# XmegaA4U_v2_1.net
KiCad netlist of a schematic drawn in EAGLE
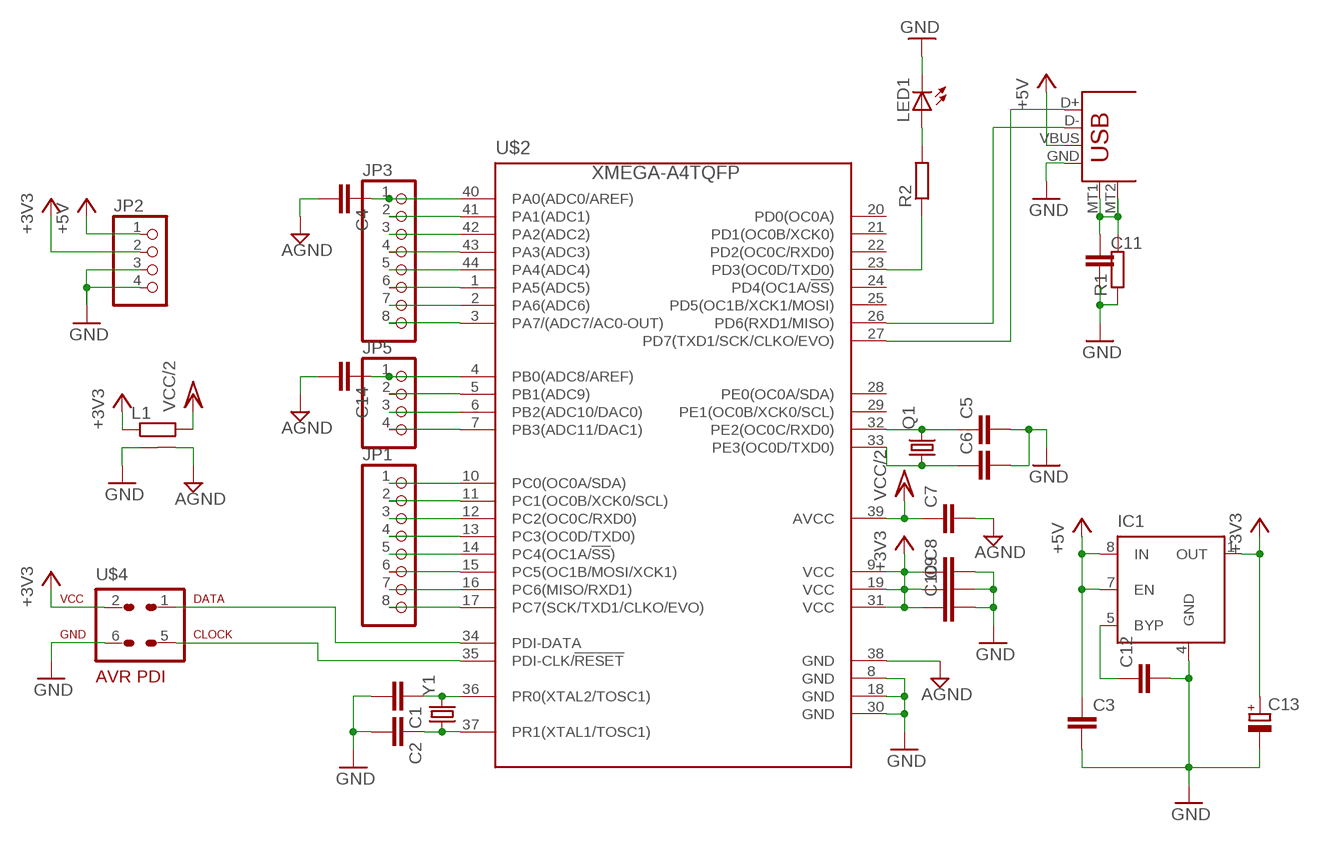
[diagram p0: schematic, sheet 1]

(export (version "E")
  (design (tool "Eeschema 10.0.6"))
  (components
    (comp (ref "C1")
      (value "C-EUC0603")
      (footprint "eagle-import:C0603")
      (libsource (lib "eagle-import") (part "C-EUC0603"))
    )
    (comp (ref "C2")
      (value "C-EUC0603")
      (footprint "eagle-import:C0603")
      (libsource (lib "eagle-import") (part "C-EUC0603"))
    )
    (comp (ref "C3")
      (value "C-EUC0805")
      (footprint "eagle-import:C0805")
      (libsource (lib "eagle-import") (part "C-EUC0805"))
    )
    (comp (ref "C4")
      (value "C-EUC0402")
      (footprint "eagle-import:C0402")
      (libsource (lib "eagle-import") (part "C-EUC0402"))
    )
    (comp (ref "C5")
      (value "C-EUC0402")
      (footprint "eagle-import:C0402")
      (libsource (lib "eagle-import") (part "C-EUC0402"))
    )
    (comp (ref "C6")
      (value "C-EUC0402")
      (footprint "eagle-import:C0402")
      (libsource (lib "eagle-import") (part "C-EUC0402"))
    )
    (comp (ref "C7")
      (value "C-EUC0603")
      (footprint "eagle-import:C0603")
      (libsource (lib "eagle-import") (part "C-EUC0603"))
    )
    (comp (ref "C8")
      (value "C-EUC0603")
      (footprint "eagle-import:C0603")
      (libsource (lib "eagle-import") (part "C-EUC0603"))
    )
    (comp (ref "C9")
      (value "C-EUC0603")
      (footprint "eagle-import:C0603")
      (libsource (lib "eagle-import") (part "C-EUC0603"))
    )
    (comp (ref "C10")
      (value "C-EUC0603")
      (footprint "eagle-import:C0603")
      (libsource (lib "eagle-import") (part "C-EUC0603"))
    )
    (comp (ref "C11")
      (value "C-EUC0603")
      (footprint "eagle-import:C0603")
      (libsource (lib "eagle-import") (part "C-EUC0603"))
    )
    (comp (ref "C12")
      (value "C-EUC0603")
      (footprint "eagle-import:C0603")
      (libsource (lib "eagle-import") (part "C-EUC0603"))
    )
    (comp (ref "C13")
      (value "CPOL-EUSMCA")
      (footprint "eagle-import:SMC_A")
      (libsource (lib "eagle-import") (part "CPOL-EUSMCA"))
    )
    (comp (ref "C14")
      (value "C-EUC0402")
      (footprint "eagle-import:C0402")
      (libsource (lib "eagle-import") (part "C-EUC0402"))
    )
    (comp (ref "IC1")
      (value "TC1269")
      (footprint "eagle-import:MSOP08")
      (libsource (lib "eagle-import") (part "TC1269"))
    )
    (comp (ref "JP1")
      (value "PINHD_FIXEDPAD_ROUND-1X8")
      (footprint "eagle-import:1X08_ROUND")
      (libsource (lib "eagle-import") (part "PINHD_FIXEDPAD_ROUND-1X8"))
    )
    (comp (ref "JP2")
      (value "PINHD_FIXEDPAD_ROUND-1X4")
      (footprint "eagle-import:1X04_ROUND")
      (libsource (lib "eagle-import") (part "PINHD_FIXEDPAD_ROUND-1X4"))
    )
    (comp (ref "JP3")
      (value "PINHD_FIXEDPAD_ROUND-1X8")
      (footprint "eagle-import:1X08_ROUND")
      (libsource (lib "eagle-import") (part "PINHD_FIXEDPAD_ROUND-1X8"))
    )
    (comp (ref "JP5")
      (value "PINHD_FIXEDPAD_ROUND-1X4")
      (footprint "eagle-import:1X04_ROUND")
      (libsource (lib "eagle-import") (part "PINHD_FIXEDPAD_ROUND-1X4"))
    )
    (comp (ref "L1")
      (value "R-EU_R0603")
      (footprint "eagle-import:R0603")
      (libsource (lib "eagle-import") (part "R-EU_R0603"))
    )
    (comp (ref "LED1")
      (value "LEDCHIP-LED0603")
      (footprint "eagle-import:CHIP-LED0603")
      (libsource (lib "eagle-import") (part "LEDCHIP-LED0603"))
    )
    (comp (ref "Q1")
      (value "CRYSTALTC26V_1.00")
      (footprint "eagle-import:TC26V_1.00")
      (libsource (lib "eagle-import") (part "CRYSTALTC26V_1.00"))
    )
    (comp (ref "R1")
      (value "R-EU_R0603")
      (footprint "eagle-import:R0603")
      (libsource (lib "eagle-import") (part "R-EU_R0603"))
    )
    (comp (ref "R2")
      (value "R-EU_R0603")
      (footprint "eagle-import:R0603")
      (libsource (lib "eagle-import") (part "R-EU_R0603"))
    )
    (comp (ref "U$1")
      (value "LINE1.27X0.254MM")
      (footprint "eagle-import:LINE-1.27X0.254MM")
      (libsource (lib "eagle-import") (part "LINE1.27X0.254MM"))
    )
    (comp (ref "U$2")
      (value "XMEGA-A4TQFP")
      (footprint "eagle-import:TQFP44")
      (libsource (lib "eagle-import") (part "XMEGA-A4TQFP"))
    )
    (comp (ref "U$4")
      (value "AVR-PDIFIXED")
      (footprint "eagle-import:2X03_FIXED")
      (libsource (lib "eagle-import") (part "AVR-PDIFIXED"))
    )
    (comp (ref "U$5")
      (value "USB+SHIELDMICRO")
      (footprint "eagle-import:USB-MICROB")
      (libsource (lib "eagle-import") (part "USB+SHIELDMICRO"))
    )
    (comp (ref "Y1")
      (value "CRYSTAL5X3")
      (footprint "eagle-import:CRYSTAL-SMD-5X3")
      (libsource (lib "eagle-import") (part "CRYSTAL5X3"))
    )
  )
  (nets
    (net (code "1") (name "+3V3") (class "Default")
      (node (ref "C10") (pin "1") (pinfunction "1_1") (pintype "passive"))
      (node (ref "C13") (pin "+") (pinfunction "+_+") (pintype "passive"))
      (node (ref "C8") (pin "1") (pinfunction "1_1") (pintype "passive"))
      (node (ref "C9") (pin "1") (pinfunction "1_1") (pintype "passive"))
      (node (ref "IC1") (pin "1") (pinfunction "OUT_1") (pintype "output"))
      (node (ref "JP2") (pin "2") (pinfunction "2_2") (pintype "passive"))
      (node (ref "L1") (pin "1") (pinfunction "1_1") (pintype "passive"))
      (node (ref "U$2") (pin "19") (pinfunction "VCC_19") (pintype "power_in"))
      (node (ref "U$2") (pin "31") (pinfunction "VCC_31") (pintype "power_in"))
      (node (ref "U$2") (pin "9") (pinfunction "VCC_9") (pintype "power_in"))
      (node (ref "U$4") (pin "2") (pinfunction "2_VCC_2") (pintype "passive"))
    )
    (net (code "2") (name "+5V") (class "Default")
      (node (ref "C3") (pin "1") (pinfunction "1_1") (pintype "passive"))
      (node (ref "IC1") (pin "7") (pinfunction "EN_7") (pintype "input"))
      (node (ref "IC1") (pin "8") (pinfunction "IN_8") (pintype "input"))
      (node (ref "JP2") (pin "1") (pinfunction "1_1") (pintype "passive"))
      (node (ref "U$5") (pin "VBUS") (pinfunction "VBUS_VBUS") (pintype "bidirectional"))
    )
    (net (code "3") (name "AGND") (class "Default")
      (node (ref "C14") (pin "2") (pinfunction "2_2") (pintype "passive"))
      (node (ref "C4") (pin "2") (pinfunction "2_2") (pintype "passive"))
      (node (ref "C7") (pin "2") (pinfunction "2_2") (pintype "passive"))
      (node (ref "U$1") (pin "P$2") (pinfunction "P$2_P$2") (pintype "bidirectional"))
      (node (ref "U$2") (pin "38") (pinfunction "GND_38") (pintype "power_in"))
    )
    (net (code "4") (name "GND") (class "Default")
      (node (ref "C1") (pin "2") (pinfunction "2_2") (pintype "passive"))
      (node (ref "C10") (pin "2") (pinfunction "2_2") (pintype "passive"))
      (node (ref "C11") (pin "2") (pinfunction "2_2") (pintype "passive"))
      (node (ref "C12") (pin "2") (pinfunction "2_2") (pintype "passive"))
      (node (ref "C13") (pin "-") (pinfunction "-_-") (pintype "passive"))
      (node (ref "C2") (pin "2") (pinfunction "2_2") (pintype "passive"))
      (node (ref "C3") (pin "2") (pinfunction "2_2") (pintype "passive"))
      (node (ref "C5") (pin "2") (pinfunction "2_2") (pintype "passive"))
      (node (ref "C6") (pin "2") (pinfunction "2_2") (pintype "passive"))
      (node (ref "C8") (pin "2") (pinfunction "2_2") (pintype "passive"))
      (node (ref "C9") (pin "2") (pinfunction "2_2") (pintype "passive"))
      (node (ref "IC1") (pin "4") (pinfunction "GND_4") (pintype "power_in"))
      (node (ref "JP2") (pin "3") (pinfunction "3_3") (pintype "passive"))
      (node (ref "JP2") (pin "4") (pinfunction "4_4") (pintype "passive"))
      (node (ref "LED1") (pin "C") (pinfunction "C_C") (pintype "passive"))
      (node (ref "R1") (pin "1") (pinfunction "1_1") (pintype "passive"))
      (node (ref "U$1") (pin "P$1") (pinfunction "P$1_P$1") (pintype "bidirectional"))
      (node (ref "U$2") (pin "18") (pinfunction "GND_18") (pintype "power_in"))
      (node (ref "U$2") (pin "30") (pinfunction "GND_30") (pintype "power_in"))
      (node (ref "U$2") (pin "8") (pinfunction "GND_8") (pintype "power_in"))
      (node (ref "U$4") (pin "6") (pinfunction "6_GND_6") (pintype "passive"))
      (node (ref "U$5") (pin "GND") (pinfunction "GND_GND") (pintype "bidirectional"))
    )
    (net (code "5") (name "Net-(IC1-BYP)") (class "Default")
      (node (ref "C12") (pin "1") (pinfunction "1_1") (pintype "passive"))
      (node (ref "IC1") (pin "5") (pinfunction "BYP_5") (pintype "passive"))
    )
    (net (code "6") (name "Net-(LED1-PadA)") (class "Default")
      (node (ref "LED1") (pin "A") (pinfunction "A_A") (pintype "passive"))
      (node (ref "R2") (pin "2") (pinfunction "2_2") (pintype "passive"))
    )
    (net (code "7") (name "Net-(U$2-PA0(ADC0{slash}AREF))") (class "Default")
      (node (ref "C4") (pin "1") (pinfunction "1_1") (pintype "passive"))
      (node (ref "JP3") (pin "1") (pinfunction "1_1") (pintype "passive"))
      (node (ref "U$2") (pin "40") (pinfunction "PA0(ADC0/AREF)_40") (pintype "bidirectional"))
    )
    (net (code "8") (name "Net-(U$2-PA1(ADC1))") (class "Default")
      (node (ref "JP3") (pin "2") (pinfunction "2_2") (pintype "passive"))
      (node (ref "U$2") (pin "41") (pinfunction "PA1(ADC1)_41") (pintype "bidirectional"))
    )
    (net (code "9") (name "Net-(U$2-PA2(ADC2))") (class "Default")
      (node (ref "JP3") (pin "3") (pinfunction "3_3") (pintype "passive"))
      (node (ref "U$2") (pin "42") (pinfunction "PA2(ADC2)_42") (pintype "bidirectional"))
    )
    (net (code "10") (name "Net-(U$2-PA3(ADC3))") (class "Default")
      (node (ref "JP3") (pin "4") (pinfunction "4_4") (pintype "passive"))
      (node (ref "U$2") (pin "43") (pinfunction "PA3(ADC3)_43") (pintype "bidirectional"))
    )
    (net (code "11") (name "Net-(U$2-PA4(ADC4))") (class "Default")
      (node (ref "JP3") (pin "5") (pinfunction "5_5") (pintype "passive"))
      (node (ref "U$2") (pin "44") (pinfunction "PA4(ADC4)_44") (pintype "bidirectional"))
    )
    (net (code "12") (name "Net-(U$2-PA5(ADC5))") (class "Default")
      (node (ref "JP3") (pin "6") (pinfunction "6_6") (pintype "passive"))
      (node (ref "U$2") (pin "1") (pinfunction "PA5(ADC5)_1") (pintype "bidirectional"))
    )
    (net (code "13") (name "Net-(U$2-PA6(ADC6))") (class "Default")
      (node (ref "JP3") (pin "7") (pinfunction "7_7") (pintype "passive"))
      (node (ref "U$2") (pin "2") (pinfunction "PA6(ADC6)_2") (pintype "bidirectional"))
    )
    (net (code "14") (name "Net-(U$2-PA7{slash}(ADC7{slash}AC0-OUT))") (class "Default")
      (node (ref "JP3") (pin "8") (pinfunction "8_8") (pintype "passive"))
      (node (ref "U$2") (pin "3") (pinfunction "PA7/(ADC7/AC0-OUT)_3") (pintype "bidirectional"))
    )
    (net (code "15") (name "Net-(U$2-PB0(ADC8{slash}AREF))") (class "Default")
      (node (ref "C14") (pin "1") (pinfunction "1_1") (pintype "passive"))
      (node (ref "JP5") (pin "1") (pinfunction "1_1") (pintype "passive"))
      (node (ref "U$2") (pin "4") (pinfunction "PB0(ADC8/AREF)_4") (pintype "bidirectional"))
    )
    (net (code "16") (name "Net-(U$2-PB1(ADC9))") (class "Default")
      (node (ref "JP5") (pin "2") (pinfunction "2_2") (pintype "passive"))
      (node (ref "U$2") (pin "5") (pinfunction "PB1(ADC9)_5") (pintype "bidirectional"))
    )
    (net (code "17") (name "Net-(U$2-PB2(ADC10{slash}DAC0))") (class "Default")
      (node (ref "JP5") (pin "3") (pinfunction "3_3") (pintype "passive"))
      (node (ref "U$2") (pin "6") (pinfunction "PB2(ADC10/DAC0)_6") (pintype "bidirectional"))
    )
    (net (code "18") (name "Net-(U$2-PB3(ADC11{slash}DAC1))") (class "Default")
      (node (ref "JP5") (pin "4") (pinfunction "4_4") (pintype "passive"))
      (node (ref "U$2") (pin "7") (pinfunction "PB3(ADC11/DAC1)_7") (pintype "bidirectional"))
    )
    (net (code "19") (name "Net-(U$2-PC0(OC0A{slash}SDA))") (class "Default")
      (node (ref "JP1") (pin "1") (pinfunction "1_1") (pintype "passive"))
      (node (ref "U$2") (pin "10") (pinfunction "PC0(OC0A/SDA)_10") (pintype "bidirectional"))
    )
    (net (code "20") (name "Net-(U$2-PC1(OC0B{slash}XCK0{slash}SCL))") (class "Default")
      (node (ref "JP1") (pin "2") (pinfunction "2_2") (pintype "passive"))
      (node (ref "U$2") (pin "11") (pinfunction "PC1(OC0B/XCK0/SCL)_11") (pintype "bidirectional"))
    )
    (net (code "21") (name "Net-(U$2-PC2(OC0C{slash}RXD0))") (class "Default")
      (node (ref "JP1") (pin "3") (pinfunction "3_3") (pintype "passive"))
      (node (ref "U$2") (pin "12") (pinfunction "PC2(OC0C/RXD0)_12") (pintype "bidirectional"))
    )
    (net (code "22") (name "Net-(U$2-PC3(OC0D{slash}TXD0))") (class "Default")
      (node (ref "JP1") (pin "4") (pinfunction "4_4") (pintype "passive"))
      (node (ref "U$2") (pin "13") (pinfunction "PC3(OC0D/TXD0)_13") (pintype "bidirectional"))
    )
    (net (code "23") (name "Net-(U$2-PC4(OC1A{slash}~{SS}))") (class "Default")
      (node (ref "JP1") (pin "5") (pinfunction "5_5") (pintype "passive"))
      (node (ref "U$2") (pin "14") (pinfunction "PC4(OC1A/~{SS})_14") (pintype "bidirectional"))
    )
    (net (code "24") (name "Net-(U$2-PC5(OC1B{slash}MOSI{slash}XCK1))") (class "Default")
      (node (ref "JP1") (pin "6") (pinfunction "6_6") (pintype "passive"))
      (node (ref "U$2") (pin "15") (pinfunction "PC5(OC1B/MOSI/XCK1)_15") (pintype "bidirectional"))
    )
    (net (code "25") (name "Net-(U$2-PC6(MISO{slash}RXD1))") (class "Default")
      (node (ref "JP1") (pin "7") (pinfunction "7_7") (pintype "passive"))
      (node (ref "U$2") (pin "16") (pinfunction "PC6(MISO/RXD1)_16") (pintype "bidirectional"))
    )
    (net (code "26") (name "Net-(U$2-PC7(SCK{slash}TXD1{slash}CLKO{slash}EVO))") (class "Default")
      (node (ref "JP1") (pin "8") (pinfunction "8_8") (pintype "passive"))
      (node (ref "U$2") (pin "17") (pinfunction "PC7(SCK/TXD1/CLKO/EVO)_17") (pintype "bidirectional"))
    )
    (net (code "27") (name "Net-(U$2-PD3(OC0D{slash}TXD0))") (class "Default")
      (node (ref "R2") (pin "1") (pinfunction "1_1") (pintype "passive"))
      (node (ref "U$2") (pin "23") (pinfunction "PD3(OC0D/TXD0)_23") (pintype "bidirectional"))
    )
    (net (code "28") (name "Net-(U$2-PD6(RXD1{slash}MISO))") (class "Default")
      (node (ref "U$2") (pin "26") (pinfunction "PD6(RXD1/MISO)_26") (pintype "bidirectional"))
      (node (ref "U$5") (pin "D-") (pinfunction "D-_D-") (pintype "bidirectional"))
    )
    (net (code "29") (name "Net-(U$2-PD7(TXD1{slash}SCK{slash}CLKO{slash}EVO))") (class "Default")
      (node (ref "U$2") (pin "27") (pinfunction "PD7(TXD1/SCK/CLKO/EVO)_27") (pintype "bidirectional"))
      (node (ref "U$5") (pin "D+") (pinfunction "D+_D+") (pintype "bidirectional"))
    )
    (net (code "30") (name "Net-(U$2-PDI-CLK{slash}~{RESET})") (class "Default")
      (node (ref "U$2") (pin "35") (pinfunction "PDI-CLK/~{RESET}_35") (pintype "input"))
      (node (ref "U$4") (pin "5") (pinfunction "5_CLOCK_5") (pintype "passive"))
    )
    (net (code "31") (name "Net-(U$2-PDI-DATA)") (class "Default")
      (node (ref "U$2") (pin "34") (pinfunction "PDI-DATA_34") (pintype "bidirectional"))
      (node (ref "U$4") (pin "1") (pinfunction "1_DATA_1") (pintype "passive"))
    )
    (net (code "32") (name "Net-(U$2-PE2(OC0C{slash}RXD0))") (class "Default")
      (node (ref "C5") (pin "1") (pinfunction "1_1") (pintype "passive"))
      (node (ref "Q1") (pin "2") (pinfunction "2_2") (pintype "passive"))
      (node (ref "U$2") (pin "32") (pinfunction "PE2(OC0C/RXD0)_32") (pintype "bidirectional"))
    )
    (net (code "33") (name "Net-(U$2-PE3(OC0D{slash}TXD0))") (class "Default")
      (node (ref "C6") (pin "1") (pinfunction "1_1") (pintype "passive"))
      (node (ref "Q1") (pin "1") (pinfunction "1_1") (pintype "passive"))
      (node (ref "U$2") (pin "33") (pinfunction "PE3(OC0D/TXD0)_33") (pintype "bidirectional"))
    )
    (net (code "34") (name "Net-(U$2-PR0(XTAL2{slash}TOSC1))") (class "Default")
      (node (ref "C1") (pin "1") (pinfunction "1_1") (pintype "passive"))
      (node (ref "U$2") (pin "36") (pinfunction "PR0(XTAL2/TOSC1)_36") (pintype "bidirectional"))
      (node (ref "Y1") (pin "3") (pinfunction "2_3") (pintype "passive"))
    )
    (net (code "35") (name "Net-(U$2-PR1(XTAL1{slash}TOSC1))") (class "Default")
      (node (ref "C2") (pin "1") (pinfunction "1_1") (pintype "passive"))
      (node (ref "U$2") (pin "37") (pinfunction "PR1(XTAL1/TOSC1)_37") (pintype "bidirectional"))
      (node (ref "Y1") (pin "1") (pinfunction "1_1") (pintype "passive"))
    )
    (net (code "36") (name "Net-(U$5-P$1)") (class "Default")
      (node (ref "C11") (pin "1") (pinfunction "1_1") (pintype "passive"))
      (node (ref "R1") (pin "2") (pinfunction "2_2") (pintype "passive"))
      (node (ref "U$5") (pin "MT1") (pinfunction "P$1_MT1") (pintype "bidirectional"))
      (node (ref "U$5") (pin "MT2") (pinfunction "P$2_MT2") (pintype "bidirectional"))
    )
    (net (code "37") (name "VCC{slash}2") (class "Default")
      (node (ref "C7") (pin "1") (pinfunction "1_1") (pintype "passive"))
      (node (ref "L1") (pin "2") (pinfunction "2_2") (pintype "passive"))
      (node (ref "U$2") (pin "39") (pinfunction "AVCC_39") (pintype "power_in"))
    )
    (net (code "38") (name "unconnected-(U$2-PD0(OC0A)-Pad20)") (class "Default")
      (node (ref "U$2") (pin "20") (pinfunction "PD0(OC0A)_20") (pintype "bidirectional"))
    )
    (net (code "39") (name "unconnected-(U$2-PD1(OC0B{slash}XCK0)-Pad21)") (class "Default")
      (node (ref "U$2") (pin "21") (pinfunction "PD1(OC0B/XCK0)_21") (pintype "bidirectional"))
    )
    (net (code "40") (name "unconnected-(U$2-PD2(OC0C{slash}RXD0)-Pad22)") (class "Default")
      (node (ref "U$2") (pin "22") (pinfunction "PD2(OC0C/RXD0)_22") (pintype "bidirectional"))
    )
    (net (code "41") (name "unconnected-(U$2-PD4(OC1A{slash}~{SS})-Pad24)") (class "Default")
      (node (ref "U$2") (pin "24") (pinfunction "PD4(OC1A/~{SS})_24") (pintype "bidirectional"))
    )
    (net (code "42") (name "unconnected-(U$2-PD5(OC1B{slash}XCK1{slash}MOSI)-Pad25)") (class "Default")
      (node (ref "U$2") (pin "25") (pinfunction "PD5(OC1B/XCK1/MOSI)_25") (pintype "bidirectional"))
    )
    (net (code "43") (name "unconnected-(U$2-PE0(OC0A{slash}SDA)-Pad28)") (class "Default")
      (node (ref "U$2") (pin "28") (pinfunction "PE0(OC0A/SDA)_28") (pintype "bidirectional"))
    )
    (net (code "44") (name "unconnected-(U$2-PE1(OC0B{slash}XCK0{slash}SCL)-Pad29)") (class "Default")
      (node (ref "U$2") (pin "29") (pinfunction "PE1(OC0B/XCK0/SCL)_29") (pintype "bidirectional"))
    )
  )
)
